# Sheet2.net
KiCad netlist of a schematic drawn in Altium Designer
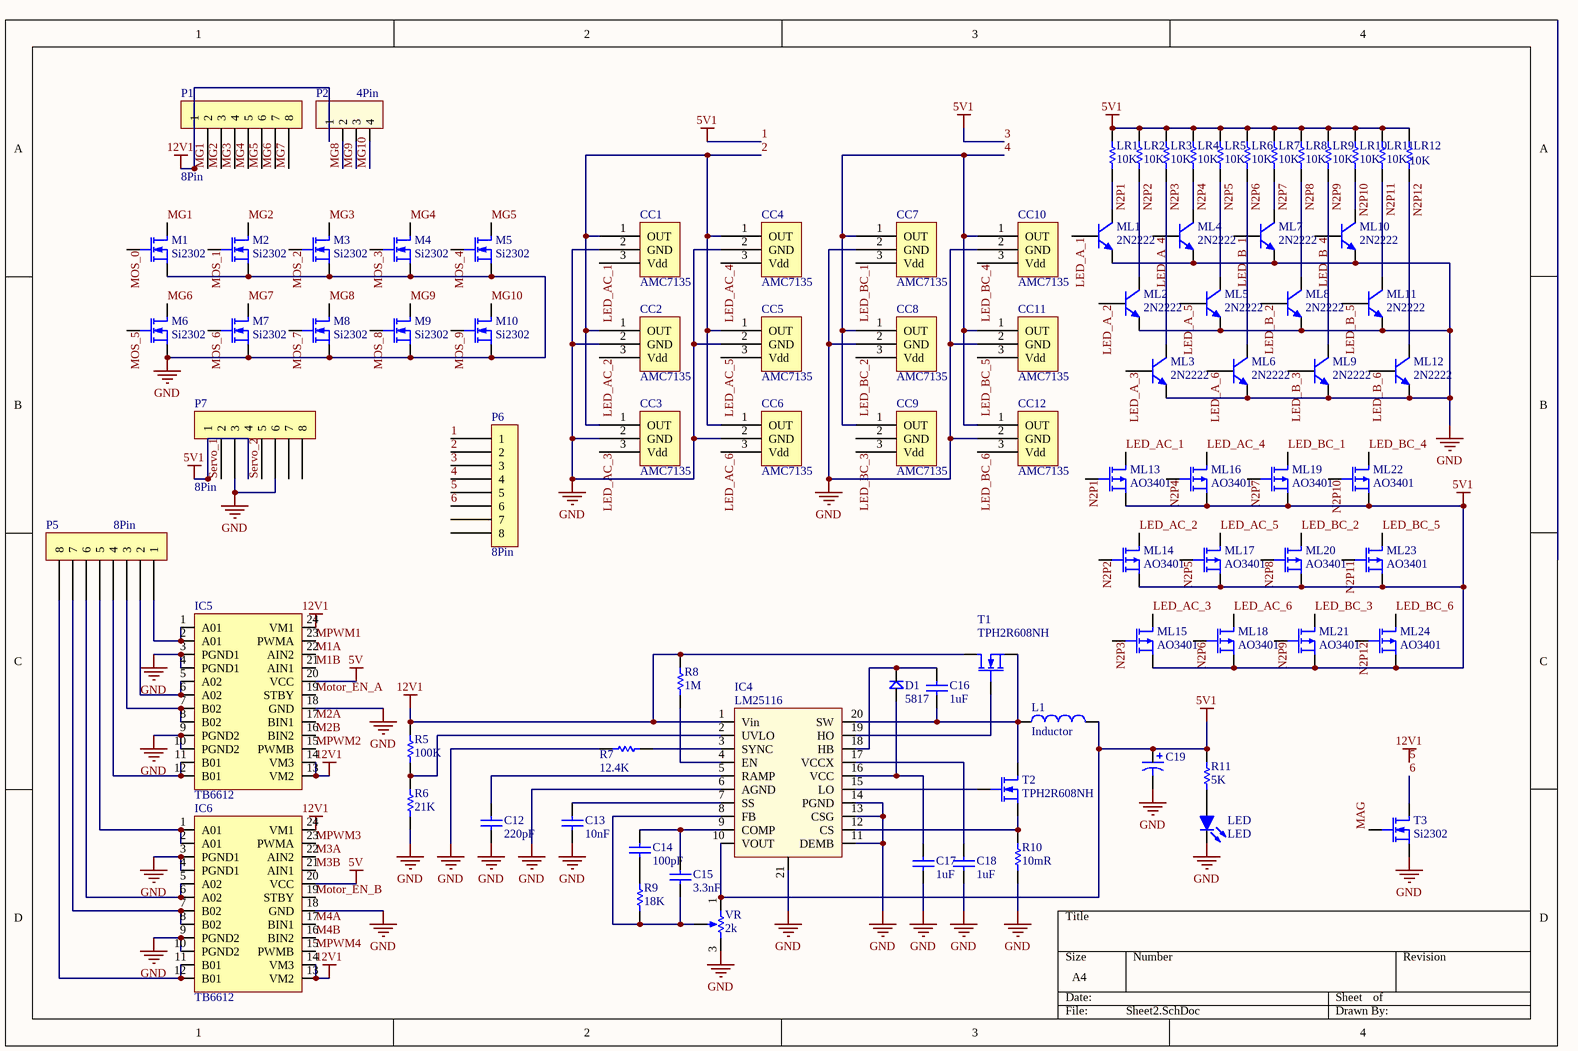
[diagram p0: Sheet2.SchDoc]

(export (version "E")
  (design (tool "Eeschema 10.0.6"))
  (components
    (comp (ref "C12") (value "220pF") (footprint "C0805") (libsource (lib "Schlib1") (part "Cap")))
    (comp (ref "C13") (value "10nF") (footprint "C0805") (libsource (lib "Schlib1") (part "Cap")))
    (comp (ref "C14") (value "100pF") (footprint "C0805") (libsource (lib "Schlib1") (part "Cap")))
    (comp (ref "C15") (value "3.3nF") (footprint "C0805") (libsource (lib "Schlib1") (part "Cap")))
    (comp (ref "C16") (value "1uF") (footprint "C0805") (libsource (lib "Schlib1") (part "Cap")))
    (comp (ref "C17") (value "1uF") (footprint "C0805") (libsource (lib "Schlib1") (part "Cap")))
    (comp (ref "C18") (value "1uF") (footprint "C0805") (libsource (lib "Schlib1") (part "Cap")))
    (comp (ref "C19")
      (value "*")
      (footprint "Cap SMD 10x12.7mm")
      (libsource (lib "Schlib1") (part "Cap-pol"))
    )
    (comp (ref "CC1")
      (value "AMC7135")
      (footprint "SOT89-150P410X160-3L")
      (libsource (lib "MyOwnSchlib_ver1.2") (part "AMC7135"))
    )
    (comp (ref "CC2")
      (value "AMC7135")
      (footprint "SOT89-150P410X160-3L")
      (libsource (lib "MyOwnSchlib_ver1.2") (part "AMC7135"))
    )
    (comp (ref "CC3")
      (value "AMC7135")
      (footprint "SOT89-150P410X160-3L")
      (libsource (lib "MyOwnSchlib_ver1.2") (part "AMC7135"))
    )
    (comp (ref "CC4")
      (value "AMC7135")
      (footprint "SOT89-150P410X160-3L")
      (libsource (lib "MyOwnSchlib_ver1.2") (part "AMC7135"))
    )
    (comp (ref "CC5")
      (value "AMC7135")
      (footprint "SOT89-150P410X160-3L")
      (libsource (lib "MyOwnSchlib_ver1.2") (part "AMC7135"))
    )
    (comp (ref "CC6")
      (value "AMC7135")
      (footprint "SOT89-150P410X160-3L")
      (libsource (lib "MyOwnSchlib_ver1.2") (part "AMC7135"))
    )
    (comp (ref "CC7")
      (value "AMC7135")
      (footprint "SOT89-150P410X160-3L")
      (libsource (lib "MyOwnSchlib_ver1.2") (part "AMC7135"))
    )
    (comp (ref "CC8")
      (value "AMC7135")
      (footprint "SOT89-150P410X160-3L")
      (libsource (lib "MyOwnSchlib_ver1.2") (part "AMC7135"))
    )
    (comp (ref "CC9")
      (value "AMC7135")
      (footprint "SOT89-150P410X160-3L")
      (libsource (lib "MyOwnSchlib_ver1.2") (part "AMC7135"))
    )
    (comp (ref "CC10")
      (value "AMC7135")
      (footprint "SOT89-150P410X160-3L")
      (libsource (lib "MyOwnSchlib_ver1.2") (part "AMC7135"))
    )
    (comp (ref "CC11")
      (value "AMC7135")
      (footprint "SOT89-150P410X160-3L")
      (libsource (lib "MyOwnSchlib_ver1.2") (part "AMC7135"))
    )
    (comp (ref "CC12")
      (value "AMC7135")
      (footprint "SOT89-150P410X160-3L")
      (libsource (lib "MyOwnSchlib_ver1.2") (part "AMC7135"))
    )
    (comp (ref "D1") (value "5817") (footprint "Diode-SOD-323") (libsource (lib "Schlib1") (part "Diode")))
    (comp (ref "IC4")
      (value "LM25116")
      (footprint "HTSSOP-20")
      (description "Buck Controller")
      (libsource (lib "Schlib1") (part "LM25116"))
    )
    (comp (ref "IC5")
      (value "TB6612")
      (footprint "SSOP24")
      (libsource (lib "MyOwnSchlib_ver1.2") (part "TB6612"))
    )
    (comp (ref "IC6")
      (value "TB6612")
      (footprint "SSOP24")
      (libsource (lib "MyOwnSchlib_ver1.2") (part "TB6612"))
    )
    (comp (ref "L1")
      (value "Inductor")
      (footprint "Inductor-CDEP147")
      (libsource (lib "Schlib1") (part "Inductor"))
    )
    (comp (ref "LED") (value "LED") (footprint "LED-0805") (libsource (lib "Schlib1") (part "LED")))
    (comp (ref "LR1")
      (value "10K")
      (footprint "R0805")
      (libsource (lib "MyOwnSchlib_ver1.2") (part "Resistor"))
    )
    (comp (ref "LR2")
      (value "10K")
      (footprint "R0805")
      (libsource (lib "MyOwnSchlib_ver1.2") (part "Resistor"))
    )
    (comp (ref "LR3")
      (value "10K")
      (footprint "R0805")
      (libsource (lib "MyOwnSchlib_ver1.2") (part "Resistor"))
    )
    (comp (ref "LR4")
      (value "10K")
      (footprint "R0805")
      (libsource (lib "MyOwnSchlib_ver1.2") (part "Resistor"))
    )
    (comp (ref "LR5")
      (value "10K")
      (footprint "R0805")
      (libsource (lib "MyOwnSchlib_ver1.2") (part "Resistor"))
    )
    (comp (ref "LR6")
      (value "10K")
      (footprint "R0805")
      (libsource (lib "MyOwnSchlib_ver1.2") (part "Resistor"))
    )
    (comp (ref "LR7")
      (value "10K")
      (footprint "R0805")
      (libsource (lib "MyOwnSchlib_ver1.2") (part "Resistor"))
    )
    (comp (ref "LR8")
      (value "10K")
      (footprint "R0805")
      (libsource (lib "MyOwnSchlib_ver1.2") (part "Resistor"))
    )
    (comp (ref "LR9")
      (value "10K")
      (footprint "R0805")
      (libsource (lib "MyOwnSchlib_ver1.2") (part "Resistor"))
    )
    (comp (ref "LR10")
      (value "10K")
      (footprint "R0805")
      (libsource (lib "MyOwnSchlib_ver1.2") (part "Resistor"))
    )
    (comp (ref "LR11")
      (value "10K")
      (footprint "R0805")
      (libsource (lib "MyOwnSchlib_ver1.2") (part "Resistor"))
    )
    (comp (ref "LR12")
      (value "10K")
      (footprint "R0805")
      (libsource (lib "MyOwnSchlib_ver1.2") (part "Resistor"))
    )
    (comp (ref "M1")
      (value "Si2302")
      (footprint "SOT23")
      (libsource (lib "MyOwnSchlib_ver1.2") (part "Si2302"))
    )
    (comp (ref "M2")
      (value "Si2302")
      (footprint "SOT23")
      (libsource (lib "MyOwnSchlib_ver1.2") (part "Si2302"))
    )
    (comp (ref "M3")
      (value "Si2302")
      (footprint "SOT23")
      (libsource (lib "MyOwnSchlib_ver1.2") (part "Si2302"))
    )
    (comp (ref "M4")
      (value "Si2302")
      (footprint "SOT23")
      (libsource (lib "MyOwnSchlib_ver1.2") (part "Si2302"))
    )
    (comp (ref "M5")
      (value "Si2302")
      (footprint "SOT23")
      (libsource (lib "MyOwnSchlib_ver1.2") (part "Si2302"))
    )
    (comp (ref "M6")
      (value "Si2302")
      (footprint "SOT23")
      (libsource (lib "MyOwnSchlib_ver1.2") (part "Si2302"))
    )
    (comp (ref "M7")
      (value "Si2302")
      (footprint "SOT23")
      (libsource (lib "MyOwnSchlib_ver1.2") (part "Si2302"))
    )
    (comp (ref "M8")
      (value "Si2302")
      (footprint "SOT23")
      (libsource (lib "MyOwnSchlib_ver1.2") (part "Si2302"))
    )
    (comp (ref "M9")
      (value "Si2302")
      (footprint "SOT23")
      (libsource (lib "MyOwnSchlib_ver1.2") (part "Si2302"))
    )
    (comp (ref "M10")
      (value "Si2302")
      (footprint "SOT23")
      (libsource (lib "MyOwnSchlib_ver1.2") (part "Si2302"))
    )
    (comp (ref "ML1")
      (value "2N2222")
      (footprint "SOT23")
      (description "NPN")
      (libsource (lib "MyOwnSchlib_ver1.2") (part "2N2222"))
    )
    (comp (ref "ML2")
      (value "2N2222")
      (footprint "SOT23")
      (description "NPN")
      (libsource (lib "MyOwnSchlib_ver1.2") (part "2N2222"))
    )
    (comp (ref "ML3")
      (value "2N2222")
      (footprint "SOT23")
      (description "NPN")
      (libsource (lib "MyOwnSchlib_ver1.2") (part "2N2222"))
    )
    (comp (ref "ML4")
      (value "2N2222")
      (footprint "SOT23")
      (description "NPN")
      (libsource (lib "MyOwnSchlib_ver1.2") (part "2N2222"))
    )
    (comp (ref "ML5")
      (value "2N2222")
      (footprint "SOT23")
      (description "NPN")
      (libsource (lib "MyOwnSchlib_ver1.2") (part "2N2222"))
    )
    (comp (ref "ML6")
      (value "2N2222")
      (footprint "SOT23")
      (description "NPN")
      (libsource (lib "MyOwnSchlib_ver1.2") (part "2N2222"))
    )
    (comp (ref "ML7")
      (value "2N2222")
      (footprint "SOT23")
      (description "NPN")
      (libsource (lib "MyOwnSchlib_ver1.2") (part "2N2222"))
    )
    (comp (ref "ML8")
      (value "2N2222")
      (footprint "SOT23")
      (description "NPN")
      (libsource (lib "MyOwnSchlib_ver1.2") (part "2N2222"))
    )
    (comp (ref "ML9")
      (value "2N2222")
      (footprint "SOT23")
      (description "NPN")
      (libsource (lib "MyOwnSchlib_ver1.2") (part "2N2222"))
    )
    (comp (ref "ML10")
      (value "2N2222")
      (footprint "SOT23")
      (description "NPN")
      (libsource (lib "MyOwnSchlib_ver1.2") (part "2N2222"))
    )
    (comp (ref "ML11")
      (value "2N2222")
      (footprint "SOT23")
      (description "NPN")
      (libsource (lib "MyOwnSchlib_ver1.2") (part "2N2222"))
    )
    (comp (ref "ML12")
      (value "2N2222")
      (footprint "SOT23")
      (description "NPN")
      (libsource (lib "MyOwnSchlib_ver1.2") (part "2N2222"))
    )
    (comp (ref "ML13")
      (value "AO3401")
      (footprint "SOT23")
      (libsource (lib "MyOwnSchlib_ver1.2") (part "AO3401"))
    )
    (comp (ref "ML14")
      (value "AO3401")
      (footprint "SOT23")
      (libsource (lib "MyOwnSchlib_ver1.2") (part "AO3401"))
    )
    (comp (ref "ML15")
      (value "AO3401")
      (footprint "SOT23")
      (libsource (lib "MyOwnSchlib_ver1.2") (part "AO3401"))
    )
    (comp (ref "ML16")
      (value "AO3401")
      (footprint "SOT23")
      (libsource (lib "MyOwnSchlib_ver1.2") (part "AO3401"))
    )
    (comp (ref "ML17")
      (value "AO3401")
      (footprint "SOT23")
      (libsource (lib "MyOwnSchlib_ver1.2") (part "AO3401"))
    )
    (comp (ref "ML18")
      (value "AO3401")
      (footprint "SOT23")
      (libsource (lib "MyOwnSchlib_ver1.2") (part "AO3401"))
    )
    (comp (ref "ML19")
      (value "AO3401")
      (footprint "SOT23")
      (libsource (lib "MyOwnSchlib_ver1.2") (part "AO3401"))
    )
    (comp (ref "ML20")
      (value "AO3401")
      (footprint "SOT23")
      (libsource (lib "MyOwnSchlib_ver1.2") (part "AO3401"))
    )
    (comp (ref "ML21")
      (value "AO3401")
      (footprint "SOT23")
      (libsource (lib "MyOwnSchlib_ver1.2") (part "AO3401"))
    )
    (comp (ref "ML22")
      (value "AO3401")
      (footprint "SOT23")
      (libsource (lib "MyOwnSchlib_ver1.2") (part "AO3401"))
    )
    (comp (ref "ML23")
      (value "AO3401")
      (footprint "SOT23")
      (libsource (lib "MyOwnSchlib_ver1.2") (part "AO3401"))
    )
    (comp (ref "ML24")
      (value "AO3401")
      (footprint "SOT23")
      (libsource (lib "MyOwnSchlib_ver1.2") (part "AO3401"))
    )
    (comp (ref "P1") (value "8Pin") (footprint "XH2.54-8pin_SMD") (libsource (lib "") (part "8Pin_1")))
    (comp (ref "P2")
      (value "4Pin")
      (footprint "XH2.54-4pin_SMD")
      (libsource (lib "MyOwnSchlib_ver1.2") (part "4Pin"))
    )
    (comp (ref "P5")
      (value "8Pin")
      (footprint "XH2.54-8pin_SMD")
      (libsource (lib "MyOwnSchlib_ver1.2") (part "8Pin"))
    )
    (comp (ref "P6")
      (value "8Pin")
      (footprint "XH2.54-8pin_SMD")
      (libsource (lib "MyOwnSchlib_ver1.2") (part "8Pin"))
    )
    (comp (ref "P7") (value "8Pin") (footprint "XH2.54-8pin_SMD") (libsource (lib "") (part "8Pin_1")))
    (comp (ref "R5") (value "100K") (footprint "R0805") (libsource (lib "Schlib1") (part "Resistor")))
    (comp (ref "R6") (value "21K") (footprint "R0805") (libsource (lib "Schlib1") (part "Resistor")))
    (comp (ref "R7") (value "12.4K") (footprint "R0805") (libsource (lib "Schlib1") (part "Resistor")))
    (comp (ref "R8") (value "1M") (footprint "R0805") (libsource (lib "Schlib1") (part "Resistor")))
    (comp (ref "R9") (value "18K") (footprint "R0805") (libsource (lib "Schlib1") (part "Resistor")))
    (comp (ref "R10") (value "10mR") (footprint "R2010") (libsource (lib "Schlib1") (part "Resistor")))
    (comp (ref "R11") (value "5K") (footprint "R0805") (libsource (lib "Schlib1") (part "Resistor")))
    (comp (ref "T1")
      (value "TPH2R608NH")
      (footprint "TPH2R608NH")
      (libsource (lib "Schlib1") (part "MOSFET-N"))
    )
    (comp (ref "T2")
      (value "TPH2R608NH")
      (footprint "TPH2R608NH")
      (libsource (lib "Schlib1") (part "MOSFET-N"))
    )
    (comp (ref "T3")
      (value "Si2302")
      (footprint "SOT23")
      (libsource (lib "MyOwnSchlib_ver1.2") (part "Si2302"))
    )
    (comp (ref "VR")
      (value "2k")
      (footprint "3224W-1-202E")
      (libsource (lib "Schlib1") (part "Potentiometer"))
    )
  )
  (nets
    (net (code "1") (name "/2") (class "Default")
      (node (ref "CC1") (pin "1") (pinfunction "OUT_1") (pintype "passive"))
      (node (ref "CC2") (pin "1") (pinfunction "OUT_1") (pintype "passive"))
      (node (ref "CC3") (pin "1") (pinfunction "OUT_1") (pintype "passive"))
      (node (ref "CC4") (pin "1") (pinfunction "OUT_1") (pintype "passive"))
      (node (ref "CC5") (pin "1") (pinfunction "OUT_1") (pintype "passive"))
      (node (ref "CC6") (pin "1") (pinfunction "OUT_1") (pintype "passive"))
      (node (ref "P6") (pin "2") (pinfunction "2_2") (pintype "passive"))
    )
    (net (code "2") (name "/4") (class "Default")
      (node (ref "CC10") (pin "1") (pinfunction "OUT_1") (pintype "passive"))
      (node (ref "CC11") (pin "1") (pinfunction "OUT_1") (pintype "passive"))
      (node (ref "CC12") (pin "1") (pinfunction "OUT_1") (pintype "passive"))
      (node (ref "CC7") (pin "1") (pinfunction "OUT_1") (pintype "passive"))
      (node (ref "CC8") (pin "1") (pinfunction "OUT_1") (pintype "passive"))
      (node (ref "CC9") (pin "1") (pinfunction "OUT_1") (pintype "passive"))
      (node (ref "P6") (pin "4") (pinfunction "4_4") (pintype "passive"))
    )
    (net (code "3") (name "/6") (class "Default")
      (node (ref "P6") (pin "6") (pinfunction "6_6") (pintype "passive"))
      (node (ref "T3") (pin "3") (pinfunction "D_3") (pintype "passive"))
    )
    (net (code "4") (name "/LED_AC_1") (class "Default")
      (node (ref "CC1") (pin "3") (pinfunction "Vdd_3") (pintype "passive"))
      (node (ref "ML13") (pin "3") (pinfunction "D_3") (pintype "passive"))
    )
    (net (code "5") (name "/LED_AC_2") (class "Default")
      (node (ref "CC2") (pin "3") (pinfunction "Vdd_3") (pintype "passive"))
      (node (ref "ML14") (pin "3") (pinfunction "D_3") (pintype "passive"))
    )
    (net (code "6") (name "/LED_AC_3") (class "Default")
      (node (ref "CC3") (pin "3") (pinfunction "Vdd_3") (pintype "passive"))
      (node (ref "ML15") (pin "3") (pinfunction "D_3") (pintype "passive"))
    )
    (net (code "7") (name "/LED_AC_4") (class "Default")
      (node (ref "CC4") (pin "3") (pinfunction "Vdd_3") (pintype "passive"))
      (node (ref "ML16") (pin "3") (pinfunction "D_3") (pintype "passive"))
    )
    (net (code "8") (name "/LED_AC_5") (class "Default")
      (node (ref "CC5") (pin "3") (pinfunction "Vdd_3") (pintype "passive"))
      (node (ref "ML17") (pin "3") (pinfunction "D_3") (pintype "passive"))
    )
    (net (code "9") (name "/LED_AC_6") (class "Default")
      (node (ref "CC6") (pin "3") (pinfunction "Vdd_3") (pintype "passive"))
      (node (ref "ML18") (pin "3") (pinfunction "D_3") (pintype "passive"))
    )
    (net (code "10") (name "/LED_A_1") (class "Default")
      (node (ref "ML1") (pin "1") (pinfunction "B_1") (pintype "passive"))
    )
    (net (code "11") (name "/LED_A_2") (class "Default")
      (node (ref "ML2") (pin "1") (pinfunction "B_1") (pintype "passive"))
    )
    (net (code "12") (name "/LED_A_3") (class "Default")
      (node (ref "ML3") (pin "1") (pinfunction "B_1") (pintype "passive"))
    )
    (net (code "13") (name "/LED_A_4") (class "Default")
      (node (ref "ML4") (pin "1") (pinfunction "B_1") (pintype "passive"))
    )
    (net (code "14") (name "/LED_A_5") (class "Default")
      (node (ref "ML5") (pin "1") (pinfunction "B_1") (pintype "passive"))
    )
    (net (code "15") (name "/LED_A_6") (class "Default")
      (node (ref "ML6") (pin "1") (pinfunction "B_1") (pintype "passive"))
    )
    (net (code "16") (name "/LED_BC_1") (class "Default")
      (node (ref "CC7") (pin "3") (pinfunction "Vdd_3") (pintype "passive"))
      (node (ref "ML19") (pin "3") (pinfunction "D_3") (pintype "passive"))
    )
    (net (code "17") (name "/LED_BC_2") (class "Default")
      (node (ref "CC8") (pin "3") (pinfunction "Vdd_3") (pintype "passive"))
      (node (ref "ML20") (pin "3") (pinfunction "D_3") (pintype "passive"))
    )
    (net (code "18") (name "/LED_BC_3") (class "Default")
      (node (ref "CC9") (pin "3") (pinfunction "Vdd_3") (pintype "passive"))
      (node (ref "ML21") (pin "3") (pinfunction "D_3") (pintype "passive"))
    )
    (net (code "19") (name "/LED_BC_4") (class "Default")
      (node (ref "CC10") (pin "3") (pinfunction "Vdd_3") (pintype "passive"))
      (node (ref "ML22") (pin "3") (pinfunction "D_3") (pintype "passive"))
    )
    (net (code "20") (name "/LED_BC_5") (class "Default")
      (node (ref "CC11") (pin "3") (pinfunction "Vdd_3") (pintype "passive"))
      (node (ref "ML23") (pin "3") (pinfunction "D_3") (pintype "passive"))
    )
    (net (code "21") (name "/LED_BC_6") (class "Default")
      (node (ref "CC12") (pin "3") (pinfunction "Vdd_3") (pintype "passive"))
      (node (ref "ML24") (pin "3") (pinfunction "D_3") (pintype "passive"))
    )
    (net (code "22") (name "/LED_B_1") (class "Default")
      (node (ref "ML7") (pin "1") (pinfunction "B_1") (pintype "passive"))
    )
    (net (code "23") (name "/LED_B_2") (class "Default")
      (node (ref "ML8") (pin "1") (pinfunction "B_1") (pintype "passive"))
    )
    (net (code "24") (name "/LED_B_3") (class "Default")
      (node (ref "ML9") (pin "1") (pinfunction "B_1") (pintype "passive"))
    )
    (net (code "25") (name "/LED_B_4") (class "Default")
      (node (ref "ML10") (pin "1") (pinfunction "B_1") (pintype "passive"))
    )
    (net (code "26") (name "/LED_B_5") (class "Default")
      (node (ref "ML11") (pin "1") (pinfunction "B_1") (pintype "passive"))
    )
    (net (code "27") (name "/LED_B_6") (class "Default")
      (node (ref "ML12") (pin "1") (pinfunction "B_1") (pintype "passive"))
    )
    (net (code "28") (name "/M1A") (class "Default")
      (node (ref "IC5") (pin "22") (pinfunction "AIN2_22") (pintype "open_emitter"))
    )
    (net (code "29") (name "/M1B") (class "Default")
      (node (ref "IC5") (pin "21") (pinfunction "AIN1_21") (pintype "open_emitter"))
    )
    (net (code "30") (name "/M2A") (class "Default")
      (node (ref "IC5") (pin "17") (pinfunction "BIN1_17") (pintype "open_emitter"))
    )
    (net (code "31") (name "/M2B") (class "Default")
      (node (ref "IC5") (pin "16") (pinfunction "BIN2_16") (pintype "open_emitter"))
    )
    (net (code "32") (name "/M3A") (class "Default")
      (node (ref "IC6") (pin "22") (pinfunction "AIN2_22") (pintype "open_emitter"))
    )
    (net (code "33") (name "/M3B") (class "Default")
      (node (ref "IC6") (pin "21") (pinfunction "AIN1_21") (pintype "open_emitter"))
    )
    (net (code "34") (name "/M4A") (class "Default")
      (node (ref "IC6") (pin "17") (pinfunction "BIN1_17") (pintype "open_emitter"))
    )
    (net (code "35") (name "/M4B") (class "Default")
      (node (ref "IC6") (pin "16") (pinfunction "BIN2_16") (pintype "open_emitter"))
    )
    (net (code "36") (name "/MAG") (class "Default")
      (node (ref "T3") (pin "1") (pinfunction "G_1") (pintype "passive"))
    )
    (net (code "37") (name "/MG1") (class "Default")
      (node (ref "M1") (pin "3") (pinfunction "D_3") (pintype "passive"))
      (node (ref "P1") (pin "2") (pinfunction "2_2") (pintype "passive"))
    )
    (net (code "38") (name "/MG2") (class "Default")
      (node (ref "M2") (pin "3") (pinfunction "D_3") (pintype "passive"))
      (node (ref "P1") (pin "3") (pinfunction "3_3") (pintype "passive"))
    )
    (net (code "39") (name "/MG3") (class "Default")
      (node (ref "M3") (pin "3") (pinfunction "D_3") (pintype "passive"))
      (node (ref "P1") (pin "4") (pinfunction "4_4") (pintype "passive"))
    )
    (net (code "40") (name "/MG4") (class "Default")
      (node (ref "M4") (pin "3") (pinfunction "D_3") (pintype "passive"))
      (node (ref "P1") (pin "5") (pinfunction "5_5") (pintype "passive"))
    )
    (net (code "41") (name "/MG5") (class "Default")
      (node (ref "M5") (pin "3") (pinfunction "D_3") (pintype "passive"))
      (node (ref "P1") (pin "6") (pinfunction "6_6") (pintype "passive"))
    )
    (net (code "42") (name "/MG6") (class "Default")
      (node (ref "M6") (pin "3") (pinfunction "D_3") (pintype "passive"))
      (node (ref "P1") (pin "7") (pinfunction "7_7") (pintype "passive"))
    )
    (net (code "43") (name "/MG7") (class "Default")
      (node (ref "M7") (pin "3") (pinfunction "D_3") (pintype "passive"))
      (node (ref "P1") (pin "8") (pinfunction "8_8") (pintype "passive"))
    )
    (net (code "44") (name "/MG8") (class "Default")
      (node (ref "M8") (pin "3") (pinfunction "D_3") (pintype "passive"))
      (node (ref "P2") (pin "2") (pinfunction "2_2") (pintype "passive"))
    )
    (net (code "45") (name "/MG9") (class "Default")
      (node (ref "M9") (pin "3") (pinfunction "D_3") (pintype "passive"))
      (node (ref "P2") (pin "3") (pinfunction "3_3") (pintype "passive"))
    )
    (net (code "46") (name "/MG10") (class "Default")
      (node (ref "M10") (pin "3") (pinfunction "D_3") (pintype "passive"))
      (node (ref "P2") (pin "4") (pinfunction "4_4") (pintype "passive"))
    )
    (net (code "47") (name "/MOS_0") (class "Default")
      (node (ref "M1") (pin "1") (pinfunction "G_1") (pintype "passive"))
    )
    (net (code "48") (name "/MOS_1") (class "Default")
      (node (ref "M2") (pin "1") (pinfunction "G_1") (pintype "passive"))
    )
    (net (code "49") (name "/MOS_2") (class "Default")
      (node (ref "M3") (pin "1") (pinfunction "G_1") (pintype "passive"))
    )
    (net (code "50") (name "/MOS_3") (class "Default")
      (node (ref "M4") (pin "1") (pinfunction "G_1") (pintype "passive"))
    )
    (net (code "51") (name "/MOS_4") (class "Default")
      (node (ref "M5") (pin "1") (pinfunction "G_1") (pintype "passive"))
    )
    (net (code "52") (name "/MOS_5") (class "Default")
      (node (ref "M6") (pin "1") (pinfunction "G_1") (pintype "passive"))
    )
    (net (code "53") (name "/MOS_6") (class "Default")
      (node (ref "M7") (pin "1") (pinfunction "G_1") (pintype "passive"))
    )
    (net (code "54") (name "/MOS_7") (class "Default")
      (node (ref "M8") (pin "1") (pinfunction "G_1") (pintype "passive"))
    )
    (net (code "55") (name "/MOS_8") (class "Default")
      (node (ref "M9") (pin "1") (pinfunction "G_1") (pintype "passive"))
    )
    (net (code "56") (name "/MOS_9") (class "Default")
      (node (ref "M10") (pin "1") (pinfunction "G_1") (pintype "passive"))
    )
    (net (code "57") (name "/MPWM1") (class "Default")
      (node (ref "IC5") (pin "23") (pinfunction "PWMA_23") (pintype "open_emitter"))
    )
    (net (code "58") (name "/MPWM2") (class "Default")
      (node (ref "IC5") (pin "15") (pinfunction "PWMB_15") (pintype "open_emitter"))
    )
    (net (code "59") (name "/MPWM3") (class "Default")
      (node (ref "IC6") (pin "23") (pinfunction "PWMA_23") (pintype "open_emitter"))
    )
    (net (code "60") (name "/MPWM4") (class "Default")
      (node (ref "IC6") (pin "15") (pinfunction "PWMB_15") (pintype "open_emitter"))
    )
    (net (code "61") (name "/Motor_EN_A") (class "Default")
      (node (ref "IC5") (pin "19") (pinfunction "STBY_19") (pintype "open_emitter"))
    )
    (net (code "62") (name "/Motor_EN_B") (class "Default")
      (node (ref "IC6") (pin "19") (pinfunction "STBY_19") (pintype "open_emitter"))
    )
    (net (code "63") (name "/N2P1") (class "Default")
      (node (ref "LR1") (pin "1") (pinfunction "1_1") (pintype "passive"))
      (node (ref "ML1") (pin "3") (pinfunction "C_3") (pintype "passive"))
      (node (ref "ML13") (pin "1") (pinfunction "G_1") (pintype "passive"))
    )
    (net (code "64") (name "/N2P2") (class "Default")
      (node (ref "LR2") (pin "1") (pinfunction "1_1") (pintype "passive"))
      (node (ref "ML14") (pin "1") (pinfunction "G_1") (pintype "passive"))
      (node (ref "ML2") (pin "3") (pinfunction "C_3") (pintype "passive"))
    )
    (net (code "65") (name "/N2P3") (class "Default")
      (node (ref "LR3") (pin "1") (pinfunction "1_1") (pintype "passive"))
      (node (ref "ML15") (pin "1") (pinfunction "G_1") (pintype "passive"))
      (node (ref "ML3") (pin "3") (pinfunction "C_3") (pintype "passive"))
    )
    (net (code "66") (name "/N2P4") (class "Default")
      (node (ref "LR4") (pin "1") (pinfunction "1_1") (pintype "passive"))
      (node (ref "ML16") (pin "1") (pinfunction "G_1") (pintype "passive"))
      (node (ref "ML4") (pin "3") (pinfunction "C_3") (pintype "passive"))
    )
    (net (code "67") (name "/N2P5") (class "Default")
      (node (ref "LR5") (pin "1") (pinfunction "1_1") (pintype "passive"))
      (node (ref "ML17") (pin "1") (pinfunction "G_1") (pintype "passive"))
      (node (ref "ML5") (pin "3") (pinfunction "C_3") (pintype "passive"))
    )
    (net (code "68") (name "/N2P6") (class "Default")
      (node (ref "LR6") (pin "1") (pinfunction "1_1") (pintype "passive"))
      (node (ref "ML18") (pin "1") (pinfunction "G_1") (pintype "passive"))
      (node (ref "ML6") (pin "3") (pinfunction "C_3") (pintype "passive"))
    )
    (net (code "69") (name "/N2P7") (class "Default")
      (node (ref "LR7") (pin "1") (pinfunction "1_1") (pintype "passive"))
      (node (ref "ML19") (pin "1") (pinfunction "G_1") (pintype "passive"))
      (node (ref "ML7") (pin "3") (pinfunction "C_3") (pintype "passive"))
    )
    (net (code "70") (name "/N2P8") (class "Default")
      (node (ref "LR8") (pin "1") (pinfunction "1_1") (pintype "passive"))
      (node (ref "ML20") (pin "1") (pinfunction "G_1") (pintype "passive"))
      (node (ref "ML8") (pin "3") (pinfunction "C_3") (pintype "passive"))
    )
    (net (code "71") (name "/N2P9") (class "Default")
      (node (ref "LR9") (pin "1") (pinfunction "1_1") (pintype "passive"))
      (node (ref "ML21") (pin "1") (pinfunction "G_1") (pintype "passive"))
      (node (ref "ML9") (pin "3") (pinfunction "C_3") (pintype "passive"))
    )
    (net (code "72") (name "/N2P10") (class "Default")
      (node (ref "LR10") (pin "1") (pinfunction "1_1") (pintype "passive"))
      (node (ref "ML10") (pin "3") (pinfunction "C_3") (pintype "passive"))
      (node (ref "ML22") (pin "1") (pinfunction "G_1") (pintype "passive"))
    )
    (net (code "73") (name "/N2P11") (class "Default")
      (node (ref "LR11") (pin "1") (pinfunction "1_1") (pintype "passive"))
      (node (ref "ML11") (pin "3") (pinfunction "C_3") (pintype "passive"))
      (node (ref "ML23") (pin "1") (pinfunction "G_1") (pintype "passive"))
    )
    (net (code "74") (name "/N2P12") (class "Default")
      (node (ref "LR12") (pin "1") (pinfunction "1_1") (pintype "passive"))
      (node (ref "ML12") (pin "3") (pinfunction "C_3") (pintype "passive"))
      (node (ref "ML24") (pin "1") (pinfunction "G_1") (pintype "passive"))
    )
    (net (code "75") (name "/Servo_1") (class "Default")
      (node (ref "P7") (pin "2") (pinfunction "2_2") (pintype "passive"))
    )
    (net (code "76") (name "/Servo_2") (class "Default")
      (node (ref "P7") (pin "5") (pinfunction "5_5") (pintype "passive"))
    )
    (net (code "77") (name "5V") (class "Default")
      (node (ref "IC5") (pin "20") (pinfunction "VCC_20") (pintype "open_emitter"))
      (node (ref "IC6") (pin "20") (pinfunction "VCC_20") (pintype "open_emitter"))
    )
    (net (code "78") (name "5V1") (class "Default")
      (node (ref "C19") (pin "1") (pinfunction "1_1") (pintype "passive"))
      (node (ref "IC4") (pin "10") (pinfunction "VOUT_10") (pintype "passive"))
      (node (ref "L1") (pin "2") (pinfunction "2_2") (pintype "passive"))
      (node (ref "LR1") (pin "2") (pinfunction "2_2") (pintype "passive"))
      (node (ref "LR10") (pin "2") (pinfunction "2_2") (pintype "passive"))
      (node (ref "LR11") (pin "2") (pinfunction "2_2") (pintype "passive"))
      (node (ref "LR12") (pin "2") (pinfunction "2_2") (pintype "passive"))
      (node (ref "LR2") (pin "2") (pinfunction "2_2") (pintype "passive"))
      (node (ref "LR3") (pin "2") (pinfunction "2_2") (pintype "passive"))
      (node (ref "LR4") (pin "2") (pinfunction "2_2") (pintype "passive"))
      (node (ref "LR5") (pin "2") (pinfunction "2_2") (pintype "passive"))
      (node (ref "LR6") (pin "2") (pinfunction "2_2") (pintype "passive"))
      (node (ref "LR7") (pin "2") (pinfunction "2_2") (pintype "passive"))
      (node (ref "LR8") (pin "2") (pinfunction "2_2") (pintype "passive"))
      (node (ref "LR9") (pin "2") (pinfunction "2_2") (pintype "passive"))
      (node (ref "ML13") (pin "2") (pinfunction "S_2") (pintype "passive"))
      (node (ref "ML14") (pin "2") (pinfunction "S_2") (pintype "passive"))
      (node (ref "ML15") (pin "2") (pinfunction "S_2") (pintype "passive"))
      (node (ref "ML16") (pin "2") (pinfunction "S_2") (pintype "passive"))
      (node (ref "ML17") (pin "2") (pinfunction "S_2") (pintype "passive"))
      (node (ref "ML18") (pin "2") (pinfunction "S_2") (pintype "passive"))
      (node (ref "ML19") (pin "2") (pinfunction "S_2") (pintype "passive"))
      (node (ref "ML20") (pin "2") (pinfunction "S_2") (pintype "passive"))
      (node (ref "ML21") (pin "2") (pinfunction "S_2") (pintype "passive"))
      (node (ref "ML22") (pin "2") (pinfunction "S_2") (pintype "passive"))
      (node (ref "ML23") (pin "2") (pinfunction "S_2") (pintype "passive"))
      (node (ref "ML24") (pin "2") (pinfunction "S_2") (pintype "passive"))
      (node (ref "P6") (pin "1") (pinfunction "1_1") (pintype "passive"))
      (node (ref "P6") (pin "3") (pinfunction "3_3") (pintype "passive"))
      (node (ref "P7") (pin "1") (pinfunction "1_1") (pintype "passive"))
      (node (ref "P7") (pin "4") (pinfunction "4_4") (pintype "passive"))
      (node (ref "R11") (pin "2") (pinfunction "2_2") (pintype "passive"))
      (node (ref "VR") (pin "1") (pinfunction "TOP_1") (pintype "passive"))
    )
    (net (code "79") (name "12V1") (class "Default")
      (node (ref "IC4") (pin "1") (pinfunction "Vin_1") (pintype "passive"))
      (node (ref "IC5") (pin "13") (pinfunction "VM2_13") (pintype "open_emitter"))
      (node (ref "IC5") (pin "14") (pinfunction "VM3_14") (pintype "open_emitter"))
      (node (ref "IC5") (pin "24") (pinfunction "VM1_24") (pintype "open_emitter"))
      (node (ref "IC6") (pin "13") (pinfunction "VM2_13") (pintype "open_emitter"))
      (node (ref "IC6") (pin "14") (pinfunction "VM3_14") (pintype "open_emitter"))
      (node (ref "IC6") (pin "24") (pinfunction "VM1_24") (pintype "open_emitter"))
      (node (ref "P1") (pin "1") (pinfunction "1_1") (pintype "passive"))
      (node (ref "P2") (pin "1") (pinfunction "1_1") (pintype "passive"))
      (node (ref "P6") (pin "5") (pinfunction "5_5") (pintype "passive"))
      (node (ref "R5") (pin "2") (pinfunction "2_2") (pintype "passive"))
      (node (ref "R8") (pin "2") (pinfunction "2_2") (pintype "passive"))
      (node (ref "T1") (pin "1") (pinfunction "D_1") (pintype "passive"))
    )
    (net (code "80") (name "GND") (class "Default")
      (node (ref "C12") (pin "1") (pinfunction "1_1") (pintype "passive"))
      (node (ref "C13") (pin "1") (pinfunction "1_1") (pintype "passive"))
      (node (ref "C17") (pin "1") (pinfunction "1_1") (pintype "passive"))
      (node (ref "C18") (pin "1") (pinfunction "1_1") (pintype "passive"))
      (node (ref "C19") (pin "2") (pinfunction "2_2") (pintype "passive"))
      (node (ref "CC1") (pin "2") (pinfunction "GND_2") (pintype "passive"))
      (node (ref "CC10") (pin "2") (pinfunction "GND_2") (pintype "passive"))
      (node (ref "CC11") (pin "2") (pinfunction "GND_2") (pintype "passive"))
      (node (ref "CC12") (pin "2") (pinfunction "GND_2") (pintype "passive"))
      (node (ref "CC2") (pin "2") (pinfunction "GND_2") (pintype "passive"))
      (node (ref "CC3") (pin "2") (pinfunction "GND_2") (pintype "passive"))
      (node (ref "CC4") (pin "2") (pinfunction "GND_2") (pintype "passive"))
      (node (ref "CC5") (pin "2") (pinfunction "GND_2") (pintype "passive"))
      (node (ref "CC6") (pin "2") (pinfunction "GND_2") (pintype "passive"))
      (node (ref "CC7") (pin "2") (pinfunction "GND_2") (pintype "passive"))
      (node (ref "CC8") (pin "2") (pinfunction "GND_2") (pintype "passive"))
      (node (ref "IC4") (pin "11") (pinfunction "DEMB_11") (pintype "passive"))
      (node (ref "IC4") (pin "13") (pinfunction "CSG_13") (pintype "passive"))
      (node (ref "IC4") (pin "14") (pinfunction "PGND_14") (pintype "passive"))
      (node (ref "IC4") (pin "21") (pinfunction "21_21") (pintype "passive"))
      (node (ref "IC4") (pin "6") (pinfunction "AGND_6") (pintype "passive"))
      (node (ref "IC5") (pin "10") (pinfunction "PGND2_10") (pintype "open_emitter"))
      (node (ref "IC5") (pin "18") (pinfunction "GND_18") (pintype "open_emitter"))
      (node (ref "IC5") (pin "3") (pinfunction "PGND1_3") (pintype "open_emitter"))
      (node (ref "IC5") (pin "4") (pinfunction "PGND1_4") (pintype "open_emitter"))
      (node (ref "IC5") (pin "9") (pinfunction "PGND2_9") (pintype "open_emitter"))
      (node (ref "IC6") (pin "10") (pinfunction "PGND2_10") (pintype "open_emitter"))
      (node (ref "IC6") (pin "18") (pinfunction "GND_18") (pintype "open_emitter"))
      (node (ref "IC6") (pin "3") (pinfunction "PGND1_3") (pintype "open_emitter"))
      (node (ref "IC6") (pin "4") (pinfunction "PGND1_4") (pintype "open_emitter"))
      (node (ref "IC6") (pin "9") (pinfunction "PGND2_9") (pintype "open_emitter"))
      (node (ref "LED") (pin "2") (pinfunction "K_2") (pintype "passive"))
      (node (ref "M1") (pin "2") (pinfunction "S_2") (pintype "passive"))
      (node (ref "M10") (pin "2") (pinfunction "S_2") (pintype "passive"))
      (node (ref "M2") (pin "2") (pinfunction "S_2") (pintype "passive"))
      (node (ref "M3") (pin "2") (pinfunction "S_2") (pintype "passive"))
      (node (ref "M4") (pin "2") (pinfunction "S_2") (pintype "passive"))
      (node (ref "M5") (pin "2") (pinfunction "S_2") (pintype "passive"))
      (node (ref "M6") (pin "2") (pinfunction "S_2") (pintype "passive"))
      (node (ref "M7") (pin "2") (pinfunction "S_2") (pintype "passive"))
      (node (ref "M8") (pin "2") (pinfunction "S_2") (pintype "passive"))
      (node (ref "M9") (pin "2") (pinfunction "S_2") (pintype "passive"))
      (node (ref "ML1") (pin "2") (pinfunction "E_2") (pintype "passive"))
      (node (ref "ML10") (pin "2") (pinfunction "E_2") (pintype "passive"))
      (node (ref "ML11") (pin "2") (pinfunction "E_2") (pintype "passive"))
      (node (ref "ML12") (pin "2") (pinfunction "E_2") (pintype "passive"))
      (node (ref "ML2") (pin "2") (pinfunction "E_2") (pintype "passive"))
      (node (ref "ML3") (pin "2") (pinfunction "E_2") (pintype "passive"))
      (node (ref "ML4") (pin "2") (pinfunction "E_2") (pintype "passive"))
      (node (ref "ML5") (pin "2") (pinfunction "E_2") (pintype "passive"))
      (node (ref "ML6") (pin "2") (pinfunction "E_2") (pintype "passive"))
      (node (ref "ML7") (pin "2") (pinfunction "E_2") (pintype "passive"))
      (node (ref "ML8") (pin "2") (pinfunction "E_2") (pintype "passive"))
      (node (ref "ML9") (pin "2") (pinfunction "E_2") (pintype "passive"))
      (node (ref "P7") (pin "3") (pinfunction "3_3") (pintype "passive"))
      (node (ref "P7") (pin "6") (pinfunction "6_6") (pintype "passive"))
      (node (ref "R10") (pin "1") (pinfunction "1_1") (pintype "passive"))
      (node (ref "R6") (pin "1") (pinfunction "1_1") (pintype "passive"))
      (node (ref "R7") (pin "1") (pinfunction "1_1") (pintype "passive"))
      (node (ref "T3") (pin "2") (pinfunction "S_2") (pintype "passive"))
      (node (ref "VR") (pin "3") (pinfunction "BOT_3") (pintype "passive"))
    )
    (net (code "81") (name "Net-(C14-Pad1)") (class "Default")
      (node (ref "C14") (pin "1") (pinfunction "1_1") (pintype "passive"))
      (node (ref "R9") (pin "2") (pinfunction "2_2") (pintype "passive"))
    )
    (net (code "82") (name "Net-(D1-ANODE)") (class "Default")
      (node (ref "C17") (pin "2") (pinfunction "2_2") (pintype "passive"))
      (node (ref "D1") (pin "1") (pinfunction "ANODE_1") (pintype "passive"))
      (node (ref "IC4") (pin "16") (pinfunction "VCC_16") (pintype "passive"))
    )
    (net (code "83") (name "Net-(D1-KATHODE)") (class "Default")
      (node (ref "C16") (pin "2") (pinfunction "2_2") (pintype "passive"))
      (node (ref "D1") (pin "2") (pinfunction "KATHODE_2") (pintype "passive"))
      (node (ref "IC4") (pin "18") (pinfunction "HB_18") (pintype "passive"))
    )
    (net (code "84") (name "Net-(IC4-COMP)") (class "Default")
      (node (ref "C14") (pin "2") (pinfunction "2_2") (pintype "passive"))
      (node (ref "C15") (pin "2") (pinfunction "2_2") (pintype "passive"))
      (node (ref "IC4") (pin "9") (pinfunction "COMP_9") (pintype "passive"))
    )
    (net (code "85") (name "Net-(IC4-CS)") (class "Default")
      (node (ref "IC4") (pin "12") (pinfunction "CS_12") (pintype "passive"))
      (node (ref "R10") (pin "2") (pinfunction "2_2") (pintype "passive"))
      (node (ref "T2") (pin "3") (pinfunction "S_3") (pintype "passive"))
    )
    (net (code "86") (name "Net-(IC4-EN)") (class "Default")
      (node (ref "IC4") (pin "4") (pinfunction "EN_4") (pintype "passive"))
      (node (ref "R8") (pin "1") (pinfunction "1_1") (pintype "passive"))
    )
    (net (code "87") (name "Net-(IC4-FB)") (class "Default")
      (node (ref "C15") (pin "1") (pinfunction "1_1") (pintype "passive"))
      (node (ref "IC4") (pin "8") (pinfunction "FB_8") (pintype "passive"))
      (node (ref "R9") (pin "1") (pinfunction "1_1") (pintype "passive"))
      (node (ref "VR") (pin "2") (pinfunction "TAP_2") (pintype "passive"))
    )
    (net (code "88") (name "Net-(IC4-HO)") (class "Default")
      (node (ref "IC4") (pin "19") (pinfunction "HO_19") (pintype "passive"))
      (node (ref "T1") (pin "2") (pinfunction "G_2") (pintype "passive"))
    )
    (net (code "89") (name "Net-(IC4-LO)") (class "Default")
      (node (ref "IC4") (pin "15") (pinfunction "LO_15") (pintype "passive"))
      (node (ref "T2") (pin "2") (pinfunction "G_2") (pintype "passive"))
    )
    (net (code "90") (name "Net-(IC4-RAMP)") (class "Default")
      (node (ref "C12") (pin "2") (pinfunction "2_2") (pintype "passive"))
      (node (ref "IC4") (pin "5") (pinfunction "RAMP_5") (pintype "passive"))
    )
    (net (code "91") (name "Net-(IC4-SS)") (class "Default")
      (node (ref "C13") (pin "2") (pinfunction "2_2") (pintype "passive"))
      (node (ref "IC4") (pin "7") (pinfunction "SS_7") (pintype "passive"))
    )
    (net (code "92") (name "Net-(IC4-SW)") (class "Default")
      (node (ref "C16") (pin "1") (pinfunction "1_1") (pintype "passive"))
      (node (ref "IC4") (pin "20") (pinfunction "SW_20") (pintype "passive"))
      (node (ref "L1") (pin "1") (pinfunction "1_1") (pintype "passive"))
      (node (ref "T1") (pin "3") (pinfunction "S_3") (pintype "passive"))
      (node (ref "T2") (pin "1") (pinfunction "D_1") (pintype "passive"))
    )
    (net (code "93") (name "Net-(IC4-SYNC)") (class "Default")
      (node (ref "IC4") (pin "3") (pinfunction "SYNC_3") (pintype "passive"))
      (node (ref "R7") (pin "2") (pinfunction "2_2") (pintype "passive"))
    )
    (net (code "94") (name "Net-(IC4-UVLO)") (class "Default")
      (node (ref "IC4") (pin "2") (pinfunction "UVLO_2") (pintype "passive"))
      (node (ref "R5") (pin "1") (pinfunction "1_1") (pintype "passive"))
      (node (ref "R6") (pin "2") (pinfunction "2_2") (pintype "passive"))
    )
    (net (code "95") (name "Net-(IC4-VCCX)") (class "Default")
      (node (ref "C18") (pin "2") (pinfunction "2_2") (pintype "passive"))
      (node (ref "IC4") (pin "17") (pinfunction "VCCX_17") (pintype "passive"))
    )
    (net (code "96") (name "Net-(IC5-A01-Pad1)") (class "Default")
      (node (ref "IC5") (pin "1") (pinfunction "A01_1") (pintype "open_emitter"))
      (node (ref "IC5") (pin "2") (pinfunction "A01_2") (pintype "open_emitter"))
      (node (ref "P5") (pin "1") (pinfunction "1_1") (pintype "passive"))
    )
    (net (code "97") (name "Net-(IC5-A02-Pad5)") (class "Default")
      (node (ref "IC5") (pin "5") (pinfunction "A02_5") (pintype "open_emitter"))
      (node (ref "IC5") (pin "6") (pinfunction "A02_6") (pintype "open_emitter"))
      (node (ref "P5") (pin "2") (pinfunction "2_2") (pintype "passive"))
    )
    (net (code "98") (name "Net-(IC5-B01-Pad11)") (class "Default")
      (node (ref "IC5") (pin "11") (pinfunction "B01_11") (pintype "open_emitter"))
      (node (ref "IC5") (pin "12") (pinfunction "B01_12") (pintype "open_emitter"))
      (node (ref "P5") (pin "4") (pinfunction "4_4") (pintype "passive"))
    )
    (net (code "99") (name "Net-(IC5-B02-Pad7)") (class "Default")
      (node (ref "IC5") (pin "7") (pinfunction "B02_7") (pintype "open_emitter"))
      (node (ref "IC5") (pin "8") (pinfunction "B02_8") (pintype "open_emitter"))
      (node (ref "P5") (pin "3") (pinfunction "3_3") (pintype "passive"))
    )
    (net (code "100") (name "Net-(IC6-A01-Pad1)") (class "Default")
      (node (ref "IC6") (pin "1") (pinfunction "A01_1") (pintype "open_emitter"))
      (node (ref "IC6") (pin "2") (pinfunction "A01_2") (pintype "open_emitter"))
      (node (ref "P5") (pin "5") (pinfunction "5_5") (pintype "passive"))
    )
    (net (code "101") (name "Net-(IC6-A02-Pad5)") (class "Default")
      (node (ref "IC6") (pin "5") (pinfunction "A02_5") (pintype "open_emitter"))
      (node (ref "IC6") (pin "6") (pinfunction "A02_6") (pintype "open_emitter"))
      (node (ref "P5") (pin "6") (pinfunction "6_6") (pintype "passive"))
    )
    (net (code "102") (name "Net-(IC6-B01-Pad11)") (class "Default")
      (node (ref "IC6") (pin "11") (pinfunction "B01_11") (pintype "open_emitter"))
      (node (ref "IC6") (pin "12") (pinfunction "B01_12") (pintype "open_emitter"))
      (node (ref "P5") (pin "8") (pinfunction "8_8") (pintype "passive"))
    )
    (net (code "103") (name "Net-(IC6-B02-Pad7)") (class "Default")
      (node (ref "IC6") (pin "7") (pinfunction "B02_7") (pintype "open_emitter"))
      (node (ref "IC6") (pin "8") (pinfunction "B02_8") (pintype "open_emitter"))
      (node (ref "P5") (pin "7") (pinfunction "7_7") (pintype "passive"))
    )
    (net (code "104") (name "Net-(LED-A)") (class "Default")
      (node (ref "LED") (pin "1") (pinfunction "A_1") (pintype "passive"))
      (node (ref "R11") (pin "1") (pinfunction "1_1") (pintype "passive"))
    )
    (net (code "105") (name "unconnected-(CC9-GND-Pad2)") (class "Default")
      (node (ref "CC9") (pin "2") (pinfunction "GND_2") (pintype "passive"))
    )
    (net (code "106") (name "unconnected-(P6-Pad7)") (class "Default")
      (node (ref "P6") (pin "7") (pinfunction "7_7") (pintype "passive"))
    )
    (net (code "107") (name "unconnected-(P6-Pad8)") (class "Default")
      (node (ref "P6") (pin "8") (pinfunction "8_8") (pintype "passive"))
    )
    (net (code "108") (name "unconnected-(P7-Pad7)") (class "Default")
      (node (ref "P7") (pin "7") (pinfunction "7_7") (pintype "passive"))
    )
    (net (code "109") (name "unconnected-(P7-Pad8)") (class "Default")
      (node (ref "P7") (pin "8") (pinfunction "8_8") (pintype "passive"))
    )
  )
)
